# Syno_Ver1_4.net
KiCad netlist of a schematic drawn in EAGLE
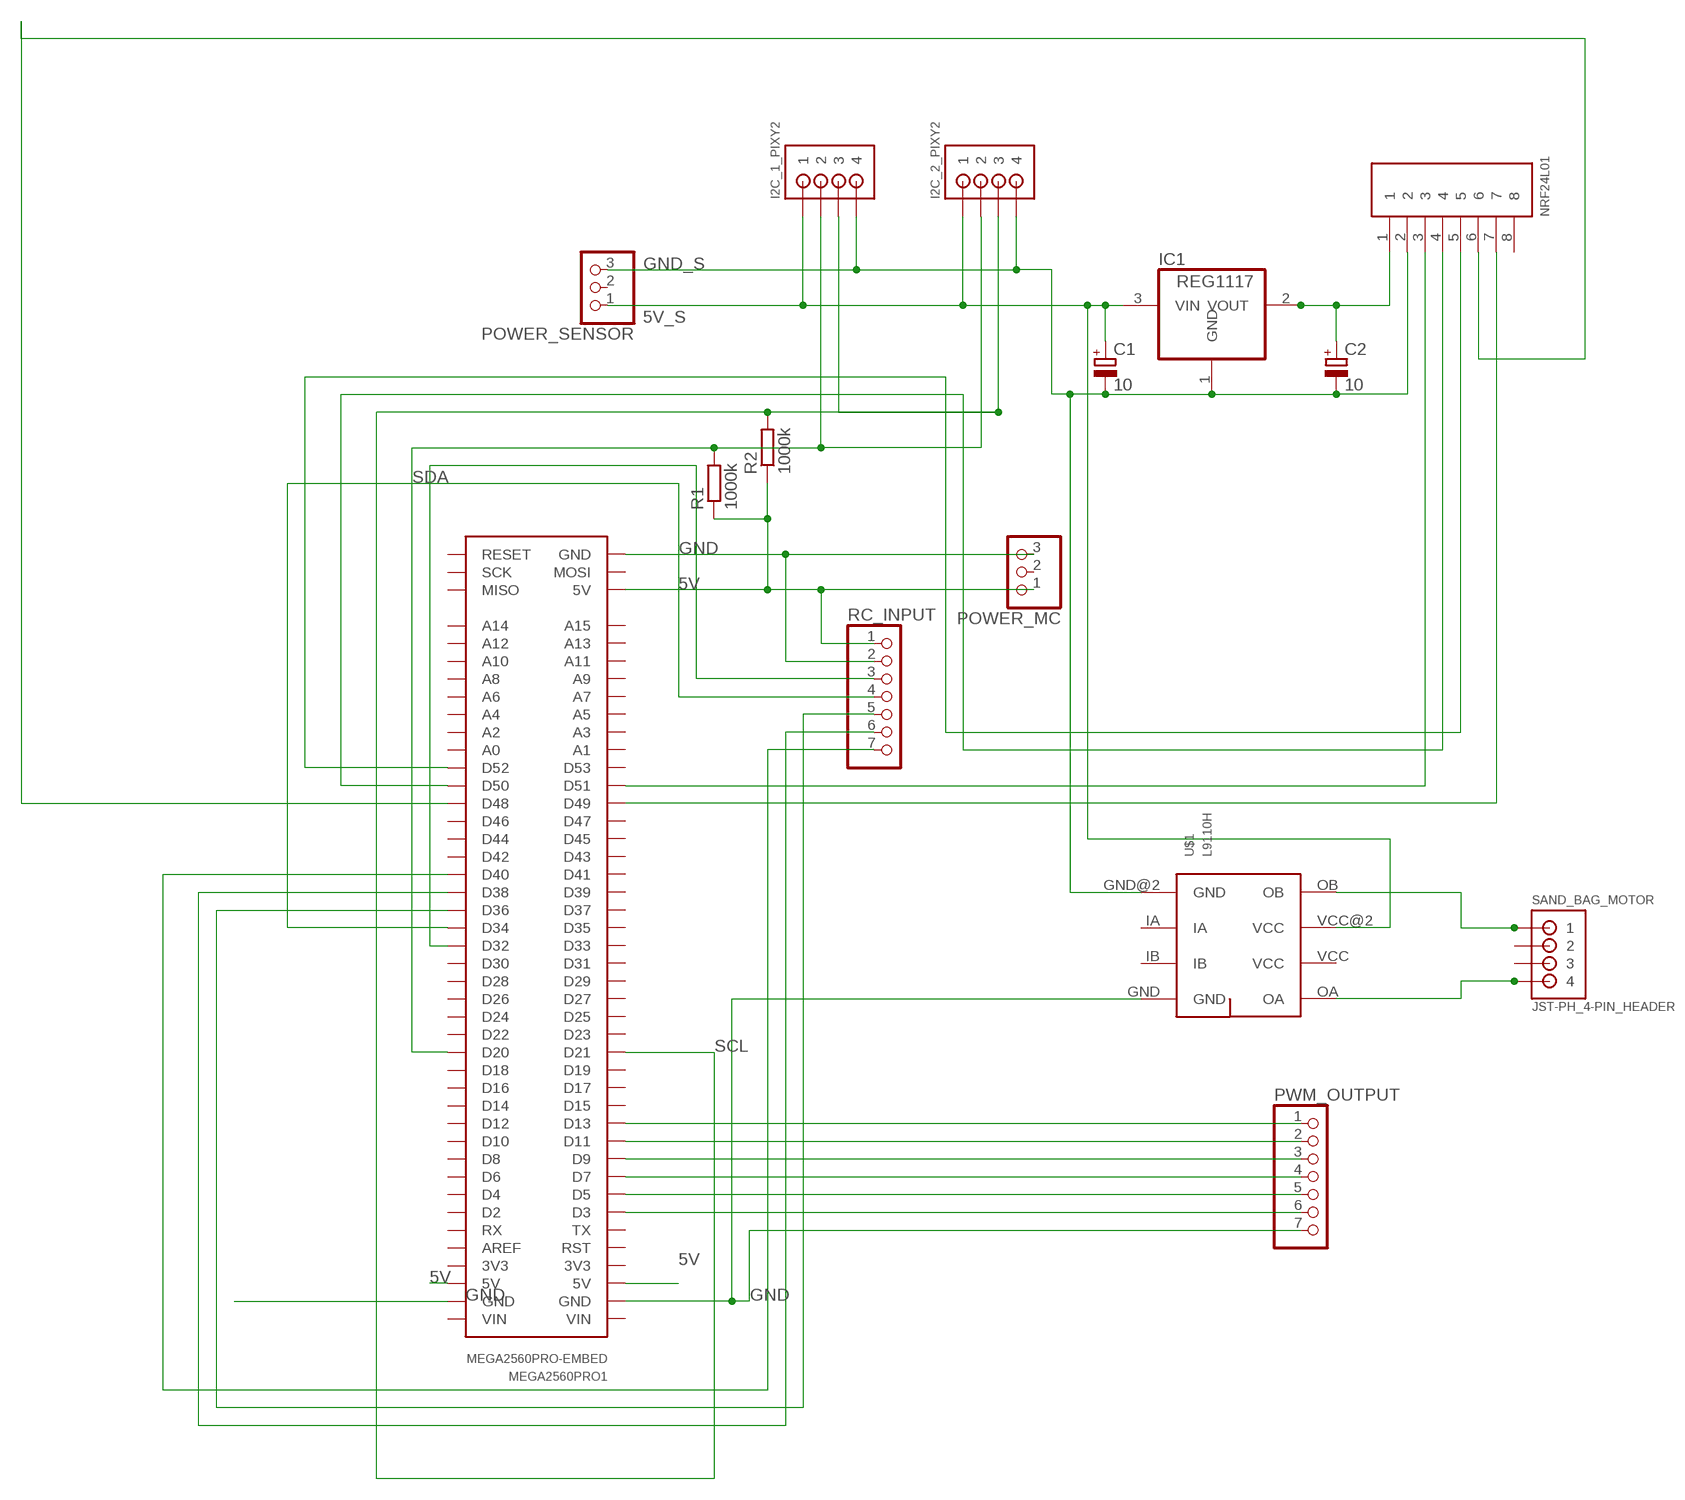
[diagram p0: schematic, sheet 1]

(export (version "E")
  (design (tool "Eeschema 10.0.6"))
  (components
    (comp (ref "C1")
      (value "10")
      (footprint "eagle-import:E1,8-4")
      (libsource (lib "eagle-import") (part "CPOL-EUE1.8-4"))
    )
    (comp (ref "C2")
      (value "10")
      (footprint "eagle-import:E1,8-4")
      (libsource (lib "eagle-import") (part "CPOL-EUE1.8-4"))
    )
    (comp (ref "I2C_1_PIXY2")
      (value "JST-PH_4-PIN_HEADER")
      (footprint "eagle-import:JST_B4B-PH_HEADER")
      (libsource (lib "eagle-import") (part "JST-PH_4-PIN_HEADER"))
    )
    (comp (ref "I2C_2_PIXY2")
      (value "JST-PH_4-PIN_HEADER")
      (footprint "eagle-import:JST_B4B-PH_HEADER")
      (libsource (lib "eagle-import") (part "JST-PH_4-PIN_HEADER"))
    )
    (comp (ref "IC1")
      (value "REG1117")
      (footprint "eagle-import:SOT223")
      (libsource (lib "eagle-import") (part "REG1117"))
    )
    (comp (ref "MEGA2560PRO1")
      (value "MEGA2560PRO-EMBED")
      (footprint "eagle-import:MEGA2560PRO-EMBED")
      (libsource (lib "eagle-import") (part "MEGA2560PRO-EMBED"))
    )
    (comp (ref "NRF24L01")
      (value "8PIN")
      (footprint "eagle-import:B8B-PH-K-S")
      (libsource (lib "eagle-import") (part "8PIN"))
    )
    (comp (ref "POWER_MC")
      (value "PINHD-1X3/90")
      (footprint "eagle-import:1X03_90")
      (libsource (lib "eagle-import") (part "PINHD-1X3/90"))
    )
    (comp (ref "POWER_SENSOR")
      (value "PINHD-1X3/90")
      (footprint "eagle-import:1X03_90")
      (libsource (lib "eagle-import") (part "PINHD-1X3/90"))
    )
    (comp (ref "PWM_OUTPUT")
      (value "PINHD-1X7/90")
      (footprint "eagle-import:1X07_90")
      (libsource (lib "eagle-import") (part "PINHD-1X7/90"))
    )
    (comp (ref "R1")
      (value "1000k")
      (footprint "eagle-import:0204_5")
      (libsource (lib "eagle-import") (part "R-EU_0204/5"))
    )
    (comp (ref "R2")
      (value "1000k")
      (footprint "eagle-import:0204_5")
      (libsource (lib "eagle-import") (part "R-EU_0204/5"))
    )
    (comp (ref "RC_INPUT")
      (value "PINHD-1X7/90")
      (footprint "eagle-import:1X07_90")
      (libsource (lib "eagle-import") (part "PINHD-1X7/90"))
    )
    (comp (ref "SAND_BAG_MOTOR")
      (value "JST-PH_4-PIN_HEADER")
      (footprint "eagle-import:JST_B4B-PH_HEADER")
      (libsource (lib "eagle-import") (part "JST-PH_4-PIN_HEADER"))
    )
    (comp (ref "U$1")
      (value "L9110H")
      (footprint "eagle-import:L9110H")
      (libsource (lib "eagle-import") (part "L9110H"))
    )
  )
  (nets
    (net (code "1") (name "/5V") (class "Default")
      (node (ref "MEGA2560PRO1") (pin "5V@1") (pinfunction "5V_5V@1") (pintype "bidirectional"))
      (node (ref "MEGA2560PRO1") (pin "5V@2") (pinfunction "5V_5V@2") (pintype "bidirectional"))
      (node (ref "MEGA2560PRO1") (pin "5V@3") (pinfunction "5V_5V@3") (pintype "bidirectional"))
      (node (ref "POWER_MC") (pin "1") (pinfunction "1_1") (pintype "passive"))
      (node (ref "R1") (pin "1") (pinfunction "1_1") (pintype "passive"))
      (node (ref "R2") (pin "1") (pinfunction "1_1") (pintype "passive"))
      (node (ref "RC_INPUT") (pin "1") (pinfunction "1_1") (pintype "passive"))
    )
    (net (code "2") (name "/5V_S") (class "Default")
      (node (ref "C1") (pin "+") (pinfunction "+_+") (pintype "passive"))
      (node (ref "I2C_1_PIXY2") (pin "P1") (pinfunction "1_P1") (pintype "bidirectional"))
      (node (ref "I2C_2_PIXY2") (pin "P1") (pinfunction "1_P1") (pintype "bidirectional"))
      (node (ref "IC1") (pin "3") (pinfunction "VIN_3") (pintype "input"))
      (node (ref "POWER_SENSOR") (pin "1") (pinfunction "1_1") (pintype "passive"))
      (node (ref "U$1") (pin "VCC@2") (pinfunction "VCC_VCC@2") (pintype "power_in"))
    )
    (net (code "3") (name "/GND") (class "Default")
      (node (ref "MEGA2560PRO1") (pin "GND@1") (pinfunction "GND_GND@1") (pintype "bidirectional"))
      (node (ref "MEGA2560PRO1") (pin "GND@2") (pinfunction "GND_GND@2") (pintype "bidirectional"))
      (node (ref "MEGA2560PRO1") (pin "GND@3") (pinfunction "GND_GND@3") (pintype "bidirectional"))
      (node (ref "POWER_MC") (pin "3") (pinfunction "3_3") (pintype "passive"))
      (node (ref "PWM_OUTPUT") (pin "7") (pinfunction "7_7") (pintype "passive"))
      (node (ref "RC_INPUT") (pin "2") (pinfunction "2_2") (pintype "passive"))
      (node (ref "U$1") (pin "GND") (pinfunction "GND_GND") (pintype "power_in"))
    )
    (net (code "4") (name "/GND_S") (class "Default")
      (node (ref "C1") (pin "-") (pinfunction "-_-") (pintype "passive"))
      (node (ref "C2") (pin "-") (pinfunction "-_-") (pintype "passive"))
      (node (ref "I2C_1_PIXY2") (pin "P4") (pinfunction "4_P4") (pintype "bidirectional"))
      (node (ref "I2C_2_PIXY2") (pin "P4") (pinfunction "4_P4") (pintype "bidirectional"))
      (node (ref "IC1") (pin "1") (pinfunction "GND_1") (pintype "power_in"))
      (node (ref "NRF24L01") (pin "2") (pinfunction "2_2") (pintype "bidirectional"))
      (node (ref "POWER_SENSOR") (pin "3") (pinfunction "3_3") (pintype "passive"))
      (node (ref "U$1") (pin "GND@2") (pinfunction "GND_GND@2") (pintype "power_in"))
    )
    (net (code "5") (name "/SCL") (class "Default")
      (node (ref "I2C_1_PIXY2") (pin "P3") (pinfunction "3_P3") (pintype "bidirectional"))
      (node (ref "I2C_2_PIXY2") (pin "P3") (pinfunction "3_P3") (pintype "bidirectional"))
      (node (ref "MEGA2560PRO1") (pin "D21") (pinfunction "D21_D21") (pintype "bidirectional"))
      (node (ref "R2") (pin "2") (pinfunction "2_2") (pintype "passive"))
    )
    (net (code "6") (name "/SDA") (class "Default")
      (node (ref "I2C_1_PIXY2") (pin "P2") (pinfunction "2_P2") (pintype "bidirectional"))
      (node (ref "I2C_2_PIXY2") (pin "P2") (pinfunction "2_P2") (pintype "bidirectional"))
      (node (ref "MEGA2560PRO1") (pin "D20") (pinfunction "D20_D20") (pintype "bidirectional"))
      (node (ref "R1") (pin "2") (pinfunction "2_2") (pintype "passive"))
    )
    (net (code "7") (name "/VCC") (class "Default")
      (node (ref "U$1") (pin "VCC") (pinfunction "VCC_VCC") (pintype "power_in"))
    )
    (net (code "8") (name "Net-(IC1-VOUT)") (class "Default")
      (node (ref "C2") (pin "+") (pinfunction "+_+") (pintype "passive"))
      (node (ref "IC1") (pin "2") (pinfunction "VOUT_2") (pintype "output"))
      (node (ref "NRF24L01") (pin "1") (pinfunction "1_1") (pintype "bidirectional"))
    )
    (net (code "9") (name "Net-(MEGA2560PRO1-PadD3)") (class "Default")
      (node (ref "MEGA2560PRO1") (pin "D3") (pinfunction "D3_D3") (pintype "bidirectional"))
      (node (ref "PWM_OUTPUT") (pin "6") (pinfunction "6_6") (pintype "passive"))
    )
    (net (code "10") (name "Net-(MEGA2560PRO1-PadD5)") (class "Default")
      (node (ref "MEGA2560PRO1") (pin "D5") (pinfunction "D5_D5") (pintype "bidirectional"))
      (node (ref "PWM_OUTPUT") (pin "5") (pinfunction "5_5") (pintype "passive"))
    )
    (net (code "11") (name "Net-(MEGA2560PRO1-PadD7)") (class "Default")
      (node (ref "MEGA2560PRO1") (pin "D7") (pinfunction "D7_D7") (pintype "bidirectional"))
      (node (ref "PWM_OUTPUT") (pin "4") (pinfunction "4_4") (pintype "passive"))
    )
    (net (code "12") (name "Net-(MEGA2560PRO1-PadD9)") (class "Default")
      (node (ref "MEGA2560PRO1") (pin "D9") (pinfunction "D9_D9") (pintype "bidirectional"))
      (node (ref "PWM_OUTPUT") (pin "3") (pinfunction "3_3") (pintype "passive"))
    )
    (net (code "13") (name "Net-(MEGA2560PRO1-PadD11)") (class "Default")
      (node (ref "MEGA2560PRO1") (pin "D11") (pinfunction "D11_D11") (pintype "bidirectional"))
      (node (ref "PWM_OUTPUT") (pin "2") (pinfunction "2_2") (pintype "passive"))
    )
    (net (code "14") (name "Net-(MEGA2560PRO1-PadD13)") (class "Default")
      (node (ref "MEGA2560PRO1") (pin "D13") (pinfunction "D13_D13") (pintype "bidirectional"))
      (node (ref "PWM_OUTPUT") (pin "1") (pinfunction "1_1") (pintype "passive"))
    )
    (net (code "15") (name "Net-(MEGA2560PRO1-PadD32)") (class "Default")
      (node (ref "MEGA2560PRO1") (pin "D32") (pinfunction "D32_D32") (pintype "bidirectional"))
      (node (ref "RC_INPUT") (pin "3") (pinfunction "3_3") (pintype "passive"))
    )
    (net (code "16") (name "Net-(MEGA2560PRO1-PadD34)") (class "Default")
      (node (ref "MEGA2560PRO1") (pin "D34") (pinfunction "D34_D34") (pintype "bidirectional"))
      (node (ref "RC_INPUT") (pin "4") (pinfunction "4_4") (pintype "passive"))
    )
    (net (code "17") (name "Net-(MEGA2560PRO1-PadD36)") (class "Default")
      (node (ref "MEGA2560PRO1") (pin "D36") (pinfunction "D36_D36") (pintype "bidirectional"))
      (node (ref "RC_INPUT") (pin "5") (pinfunction "5_5") (pintype "passive"))
    )
    (net (code "18") (name "Net-(MEGA2560PRO1-PadD38)") (class "Default")
      (node (ref "MEGA2560PRO1") (pin "D38") (pinfunction "D38_D38") (pintype "bidirectional"))
      (node (ref "RC_INPUT") (pin "6") (pinfunction "6_6") (pintype "passive"))
    )
    (net (code "19") (name "Net-(MEGA2560PRO1-PadD40)") (class "Default")
      (node (ref "MEGA2560PRO1") (pin "D40") (pinfunction "D40_D40") (pintype "bidirectional"))
      (node (ref "RC_INPUT") (pin "7") (pinfunction "7_7") (pintype "passive"))
    )
    (net (code "20") (name "Net-(MEGA2560PRO1-PadD48)") (class "Default")
      (node (ref "MEGA2560PRO1") (pin "D48") (pinfunction "D48_D48") (pintype "bidirectional"))
      (node (ref "NRF24L01") (pin "6") (pinfunction "6_6") (pintype "bidirectional"))
    )
    (net (code "21") (name "Net-(MEGA2560PRO1-PadD49)") (class "Default")
      (node (ref "MEGA2560PRO1") (pin "D49") (pinfunction "D49_D49") (pintype "bidirectional"))
      (node (ref "NRF24L01") (pin "7") (pinfunction "7_7") (pintype "bidirectional"))
    )
    (net (code "22") (name "Net-(MEGA2560PRO1-PadD50)") (class "Default")
      (node (ref "MEGA2560PRO1") (pin "D50") (pinfunction "D50_D50") (pintype "bidirectional"))
      (node (ref "NRF24L01") (pin "4") (pinfunction "4_4") (pintype "bidirectional"))
    )
    (net (code "23") (name "Net-(MEGA2560PRO1-PadD51)") (class "Default")
      (node (ref "MEGA2560PRO1") (pin "D51") (pinfunction "D51_D51") (pintype "bidirectional"))
      (node (ref "NRF24L01") (pin "3") (pinfunction "3_3") (pintype "bidirectional"))
    )
    (net (code "24") (name "Net-(MEGA2560PRO1-PadD52)") (class "Default")
      (node (ref "MEGA2560PRO1") (pin "D52") (pinfunction "D52_D52") (pintype "bidirectional"))
      (node (ref "NRF24L01") (pin "5") (pinfunction "5_5") (pintype "bidirectional"))
    )
    (net (code "25") (name "Net-(SAND_BAG_MOTOR-1)") (class "Default")
      (node (ref "SAND_BAG_MOTOR") (pin "P1") (pinfunction "1_P1") (pintype "bidirectional"))
      (node (ref "U$1") (pin "OB") (pinfunction "OB_OB") (pintype "output"))
    )
    (net (code "26") (name "Net-(SAND_BAG_MOTOR-4)") (class "Default")
      (node (ref "SAND_BAG_MOTOR") (pin "P4") (pinfunction "4_P4") (pintype "bidirectional"))
      (node (ref "U$1") (pin "OA") (pinfunction "OA_OA") (pintype "output"))
    )
    (net (code "27") (name "unconnected-(MEGA2560PRO1-3V3-Pad3V3@1)") (class "Default")
      (node (ref "MEGA2560PRO1") (pin "3V3@1") (pinfunction "3V3_3V3@1") (pintype "bidirectional"))
    )
    (net (code "28") (name "unconnected-(MEGA2560PRO1-3V3-Pad3V3@2)") (class "Default")
      (node (ref "MEGA2560PRO1") (pin "3V3@2") (pinfunction "3V3_3V3@2") (pintype "bidirectional"))
    )
    (net (code "29") (name "unconnected-(MEGA2560PRO1-PadA0)") (class "Default")
      (node (ref "MEGA2560PRO1") (pin "A0") (pinfunction "A0_A0") (pintype "bidirectional"))
    )
    (net (code "30") (name "unconnected-(MEGA2560PRO1-PadA1)") (class "Default")
      (node (ref "MEGA2560PRO1") (pin "A1") (pinfunction "A1_A1") (pintype "bidirectional"))
    )
    (net (code "31") (name "unconnected-(MEGA2560PRO1-PadA2)") (class "Default")
      (node (ref "MEGA2560PRO1") (pin "A2") (pinfunction "A2_A2") (pintype "bidirectional"))
    )
    (net (code "32") (name "unconnected-(MEGA2560PRO1-PadA3)") (class "Default")
      (node (ref "MEGA2560PRO1") (pin "A3") (pinfunction "A3_A3") (pintype "bidirectional"))
    )
    (net (code "33") (name "unconnected-(MEGA2560PRO1-PadA4)") (class "Default")
      (node (ref "MEGA2560PRO1") (pin "A4") (pinfunction "A4_A4") (pintype "bidirectional"))
    )
    (net (code "34") (name "unconnected-(MEGA2560PRO1-PadA5)") (class "Default")
      (node (ref "MEGA2560PRO1") (pin "A5") (pinfunction "A5_A5") (pintype "bidirectional"))
    )
    (net (code "35") (name "unconnected-(MEGA2560PRO1-PadA6)") (class "Default")
      (node (ref "MEGA2560PRO1") (pin "A6") (pinfunction "A6_A6") (pintype "bidirectional"))
    )
    (net (code "36") (name "unconnected-(MEGA2560PRO1-PadA7)") (class "Default")
      (node (ref "MEGA2560PRO1") (pin "A7") (pinfunction "A7_A7") (pintype "bidirectional"))
    )
    (net (code "37") (name "unconnected-(MEGA2560PRO1-PadA8)") (class "Default")
      (node (ref "MEGA2560PRO1") (pin "A8") (pinfunction "A8_A8") (pintype "bidirectional"))
    )
    (net (code "38") (name "unconnected-(MEGA2560PRO1-PadA9)") (class "Default")
      (node (ref "MEGA2560PRO1") (pin "A9") (pinfunction "A9_A9") (pintype "bidirectional"))
    )
    (net (code "39") (name "unconnected-(MEGA2560PRO1-PadA10)") (class "Default")
      (node (ref "MEGA2560PRO1") (pin "A10") (pinfunction "A10_A10") (pintype "bidirectional"))
    )
    (net (code "40") (name "unconnected-(MEGA2560PRO1-PadA11)") (class "Default")
      (node (ref "MEGA2560PRO1") (pin "A11") (pinfunction "A11_A11") (pintype "bidirectional"))
    )
    (net (code "41") (name "unconnected-(MEGA2560PRO1-PadA12)") (class "Default")
      (node (ref "MEGA2560PRO1") (pin "A12") (pinfunction "A12_A12") (pintype "bidirectional"))
    )
    (net (code "42") (name "unconnected-(MEGA2560PRO1-PadA13)") (class "Default")
      (node (ref "MEGA2560PRO1") (pin "A13") (pinfunction "A13_A13") (pintype "bidirectional"))
    )
    (net (code "43") (name "unconnected-(MEGA2560PRO1-PadA14)") (class "Default")
      (node (ref "MEGA2560PRO1") (pin "A14") (pinfunction "A14_A14") (pintype "bidirectional"))
    )
    (net (code "44") (name "unconnected-(MEGA2560PRO1-PadA15)") (class "Default")
      (node (ref "MEGA2560PRO1") (pin "A15") (pinfunction "A15_A15") (pintype "bidirectional"))
    )
    (net (code "45") (name "unconnected-(MEGA2560PRO1-PadAREF)") (class "Default")
      (node (ref "MEGA2560PRO1") (pin "AREF") (pinfunction "AREF_AREF") (pintype "bidirectional"))
    )
    (net (code "46") (name "unconnected-(MEGA2560PRO1-PadD2)") (class "Default")
      (node (ref "MEGA2560PRO1") (pin "D2") (pinfunction "D2_D2") (pintype "bidirectional"))
    )
    (net (code "47") (name "unconnected-(MEGA2560PRO1-PadD4)") (class "Default")
      (node (ref "MEGA2560PRO1") (pin "D4") (pinfunction "D4_D4") (pintype "bidirectional"))
    )
    (net (code "48") (name "unconnected-(MEGA2560PRO1-PadD6)") (class "Default")
      (node (ref "MEGA2560PRO1") (pin "D6") (pinfunction "D6_D6") (pintype "bidirectional"))
    )
    (net (code "49") (name "unconnected-(MEGA2560PRO1-PadD8)") (class "Default")
      (node (ref "MEGA2560PRO1") (pin "D8") (pinfunction "D8_D8") (pintype "bidirectional"))
    )
    (net (code "50") (name "unconnected-(MEGA2560PRO1-PadD10)") (class "Default")
      (node (ref "MEGA2560PRO1") (pin "D10") (pinfunction "D10_D10") (pintype "bidirectional"))
    )
    (net (code "51") (name "unconnected-(MEGA2560PRO1-PadD12)") (class "Default")
      (node (ref "MEGA2560PRO1") (pin "D12") (pinfunction "D12_D12") (pintype "bidirectional"))
    )
    (net (code "52") (name "unconnected-(MEGA2560PRO1-PadD14)") (class "Default")
      (node (ref "MEGA2560PRO1") (pin "D14") (pinfunction "D14_D14") (pintype "bidirectional"))
    )
    (net (code "53") (name "unconnected-(MEGA2560PRO1-PadD15)") (class "Default")
      (node (ref "MEGA2560PRO1") (pin "D15") (pinfunction "D15_D15") (pintype "bidirectional"))
    )
    (net (code "54") (name "unconnected-(MEGA2560PRO1-PadD16)") (class "Default")
      (node (ref "MEGA2560PRO1") (pin "D16") (pinfunction "D16_D16") (pintype "bidirectional"))
    )
    (net (code "55") (name "unconnected-(MEGA2560PRO1-PadD17)") (class "Default")
      (node (ref "MEGA2560PRO1") (pin "D17") (pinfunction "D17_D17") (pintype "bidirectional"))
    )
    (net (code "56") (name "unconnected-(MEGA2560PRO1-PadD18)") (class "Default")
      (node (ref "MEGA2560PRO1") (pin "D18") (pinfunction "D18_D18") (pintype "bidirectional"))
    )
    (net (code "57") (name "unconnected-(MEGA2560PRO1-PadD19)") (class "Default")
      (node (ref "MEGA2560PRO1") (pin "D19") (pinfunction "D19_D19") (pintype "bidirectional"))
    )
    (net (code "58") (name "unconnected-(MEGA2560PRO1-PadD22)") (class "Default")
      (node (ref "MEGA2560PRO1") (pin "D22") (pinfunction "D22_D22") (pintype "bidirectional"))
    )
    (net (code "59") (name "unconnected-(MEGA2560PRO1-PadD23)") (class "Default")
      (node (ref "MEGA2560PRO1") (pin "D23") (pinfunction "D23_D23") (pintype "bidirectional"))
    )
    (net (code "60") (name "unconnected-(MEGA2560PRO1-PadD24)") (class "Default")
      (node (ref "MEGA2560PRO1") (pin "D24") (pinfunction "D24_D24") (pintype "bidirectional"))
    )
    (net (code "61") (name "unconnected-(MEGA2560PRO1-PadD25)") (class "Default")
      (node (ref "MEGA2560PRO1") (pin "D25") (pinfunction "D25_D25") (pintype "bidirectional"))
    )
    (net (code "62") (name "unconnected-(MEGA2560PRO1-PadD26)") (class "Default")
      (node (ref "MEGA2560PRO1") (pin "D26") (pinfunction "D26_D26") (pintype "bidirectional"))
    )
    (net (code "63") (name "unconnected-(MEGA2560PRO1-PadD27)") (class "Default")
      (node (ref "MEGA2560PRO1") (pin "D27") (pinfunction "D27_D27") (pintype "bidirectional"))
    )
    (net (code "64") (name "unconnected-(MEGA2560PRO1-PadD28)") (class "Default")
      (node (ref "MEGA2560PRO1") (pin "D28") (pinfunction "D28_D28") (pintype "bidirectional"))
    )
    (net (code "65") (name "unconnected-(MEGA2560PRO1-PadD29)") (class "Default")
      (node (ref "MEGA2560PRO1") (pin "D29") (pinfunction "D29_D29") (pintype "bidirectional"))
    )
    (net (code "66") (name "unconnected-(MEGA2560PRO1-PadD30)") (class "Default")
      (node (ref "MEGA2560PRO1") (pin "D30") (pinfunction "D30_D30") (pintype "bidirectional"))
    )
    (net (code "67") (name "unconnected-(MEGA2560PRO1-PadD31)") (class "Default")
      (node (ref "MEGA2560PRO1") (pin "D31") (pinfunction "D31_D31") (pintype "bidirectional"))
    )
    (net (code "68") (name "unconnected-(MEGA2560PRO1-PadD33)") (class "Default")
      (node (ref "MEGA2560PRO1") (pin "D33") (pinfunction "D33_D33") (pintype "bidirectional"))
    )
    (net (code "69") (name "unconnected-(MEGA2560PRO1-PadD35)") (class "Default")
      (node (ref "MEGA2560PRO1") (pin "D35") (pinfunction "D35_D35") (pintype "bidirectional"))
    )
    (net (code "70") (name "unconnected-(MEGA2560PRO1-PadD37)") (class "Default")
      (node (ref "MEGA2560PRO1") (pin "D37") (pinfunction "D37_D37") (pintype "bidirectional"))
    )
    (net (code "71") (name "unconnected-(MEGA2560PRO1-PadD39)") (class "Default")
      (node (ref "MEGA2560PRO1") (pin "D39") (pinfunction "D39_D39") (pintype "bidirectional"))
    )
    (net (code "72") (name "unconnected-(MEGA2560PRO1-PadD41)") (class "Default")
      (node (ref "MEGA2560PRO1") (pin "D41") (pinfunction "D41_D41") (pintype "bidirectional"))
    )
    (net (code "73") (name "unconnected-(MEGA2560PRO1-PadD42)") (class "Default")
      (node (ref "MEGA2560PRO1") (pin "D42") (pinfunction "D42_D42") (pintype "bidirectional"))
    )
    (net (code "74") (name "unconnected-(MEGA2560PRO1-PadD43)") (class "Default")
      (node (ref "MEGA2560PRO1") (pin "D43") (pinfunction "D43_D43") (pintype "bidirectional"))
    )
    (net (code "75") (name "unconnected-(MEGA2560PRO1-PadD44)") (class "Default")
      (node (ref "MEGA2560PRO1") (pin "D44") (pinfunction "D44_D44") (pintype "bidirectional"))
    )
    (net (code "76") (name "unconnected-(MEGA2560PRO1-PadD45)") (class "Default")
      (node (ref "MEGA2560PRO1") (pin "D45") (pinfunction "D45_D45") (pintype "bidirectional"))
    )
    (net (code "77") (name "unconnected-(MEGA2560PRO1-PadD46)") (class "Default")
      (node (ref "MEGA2560PRO1") (pin "D46") (pinfunction "D46_D46") (pintype "bidirectional"))
    )
    (net (code "78") (name "unconnected-(MEGA2560PRO1-PadD47)") (class "Default")
      (node (ref "MEGA2560PRO1") (pin "D47") (pinfunction "D47_D47") (pintype "bidirectional"))
    )
    (net (code "79") (name "unconnected-(MEGA2560PRO1-PadD53)") (class "Default")
      (node (ref "MEGA2560PRO1") (pin "D53") (pinfunction "D53_D53") (pintype "bidirectional"))
    )
    (net (code "80") (name "unconnected-(MEGA2560PRO1-PadMISO)") (class "Default")
      (node (ref "MEGA2560PRO1") (pin "MISO") (pinfunction "MISO_MISO") (pintype "bidirectional"))
    )
    (net (code "81") (name "unconnected-(MEGA2560PRO1-PadMOSI)") (class "Default")
      (node (ref "MEGA2560PRO1") (pin "MOSI") (pinfunction "MOSI_MOSI") (pintype "bidirectional"))
    )
    (net (code "82") (name "unconnected-(MEGA2560PRO1-PadRESET)") (class "Default")
      (node (ref "MEGA2560PRO1") (pin "RESET") (pinfunction "RESET_RESET") (pintype "bidirectional"))
    )
    (net (code "83") (name "unconnected-(MEGA2560PRO1-PadRST)") (class "Default")
      (node (ref "MEGA2560PRO1") (pin "RST") (pinfunction "RST_RST") (pintype "bidirectional"))
    )
    (net (code "84") (name "unconnected-(MEGA2560PRO1-PadRX)") (class "Default")
      (node (ref "MEGA2560PRO1") (pin "RX") (pinfunction "RX_RX") (pintype "bidirectional"))
    )
    (net (code "85") (name "unconnected-(MEGA2560PRO1-PadSCK)") (class "Default")
      (node (ref "MEGA2560PRO1") (pin "SCK") (pinfunction "SCK_SCK") (pintype "bidirectional"))
    )
    (net (code "86") (name "unconnected-(MEGA2560PRO1-PadTX)") (class "Default")
      (node (ref "MEGA2560PRO1") (pin "TX") (pinfunction "TX_TX") (pintype "bidirectional"))
    )
    (net (code "87") (name "unconnected-(MEGA2560PRO1-VIN-PadVIN@1)") (class "Default")
      (node (ref "MEGA2560PRO1") (pin "VIN@1") (pinfunction "VIN_VIN@1") (pintype "bidirectional"))
    )
    (net (code "88") (name "unconnected-(MEGA2560PRO1-VIN-PadVIN@2)") (class "Default")
      (node (ref "MEGA2560PRO1") (pin "VIN@2") (pinfunction "VIN_VIN@2") (pintype "bidirectional"))
    )
    (net (code "89") (name "unconnected-(NRF24L01-Pad8)") (class "Default")
      (node (ref "NRF24L01") (pin "8") (pinfunction "8_8") (pintype "bidirectional"))
    )
    (net (code "90") (name "unconnected-(POWER_MC-Pad2)") (class "Default")
      (node (ref "POWER_MC") (pin "2") (pinfunction "2_2") (pintype "passive"))
    )
    (net (code "91") (name "unconnected-(POWER_SENSOR-Pad2)") (class "Default")
      (node (ref "POWER_SENSOR") (pin "2") (pinfunction "2_2") (pintype "passive"))
    )
    (net (code "92") (name "unconnected-(SAND_BAG_MOTOR-2-PadP2)") (class "Default")
      (node (ref "SAND_BAG_MOTOR") (pin "P2") (pinfunction "2_P2") (pintype "bidirectional"))
    )
    (net (code "93") (name "unconnected-(SAND_BAG_MOTOR-3-PadP3)") (class "Default")
      (node (ref "SAND_BAG_MOTOR") (pin "P3") (pinfunction "3_P3") (pintype "bidirectional"))
    )
    (net (code "94") (name "unconnected-(U$1-PadIA)") (class "Default")
      (node (ref "U$1") (pin "IA") (pinfunction "IA_IA") (pintype "input"))
    )
    (net (code "95") (name "unconnected-(U$1-PadIB)") (class "Default")
      (node (ref "U$1") (pin "IB") (pinfunction "IB_IB") (pintype "input"))
    )
  )
)
